# GSM.net
KiCad netlist of a schematic drawn in Altium Designer
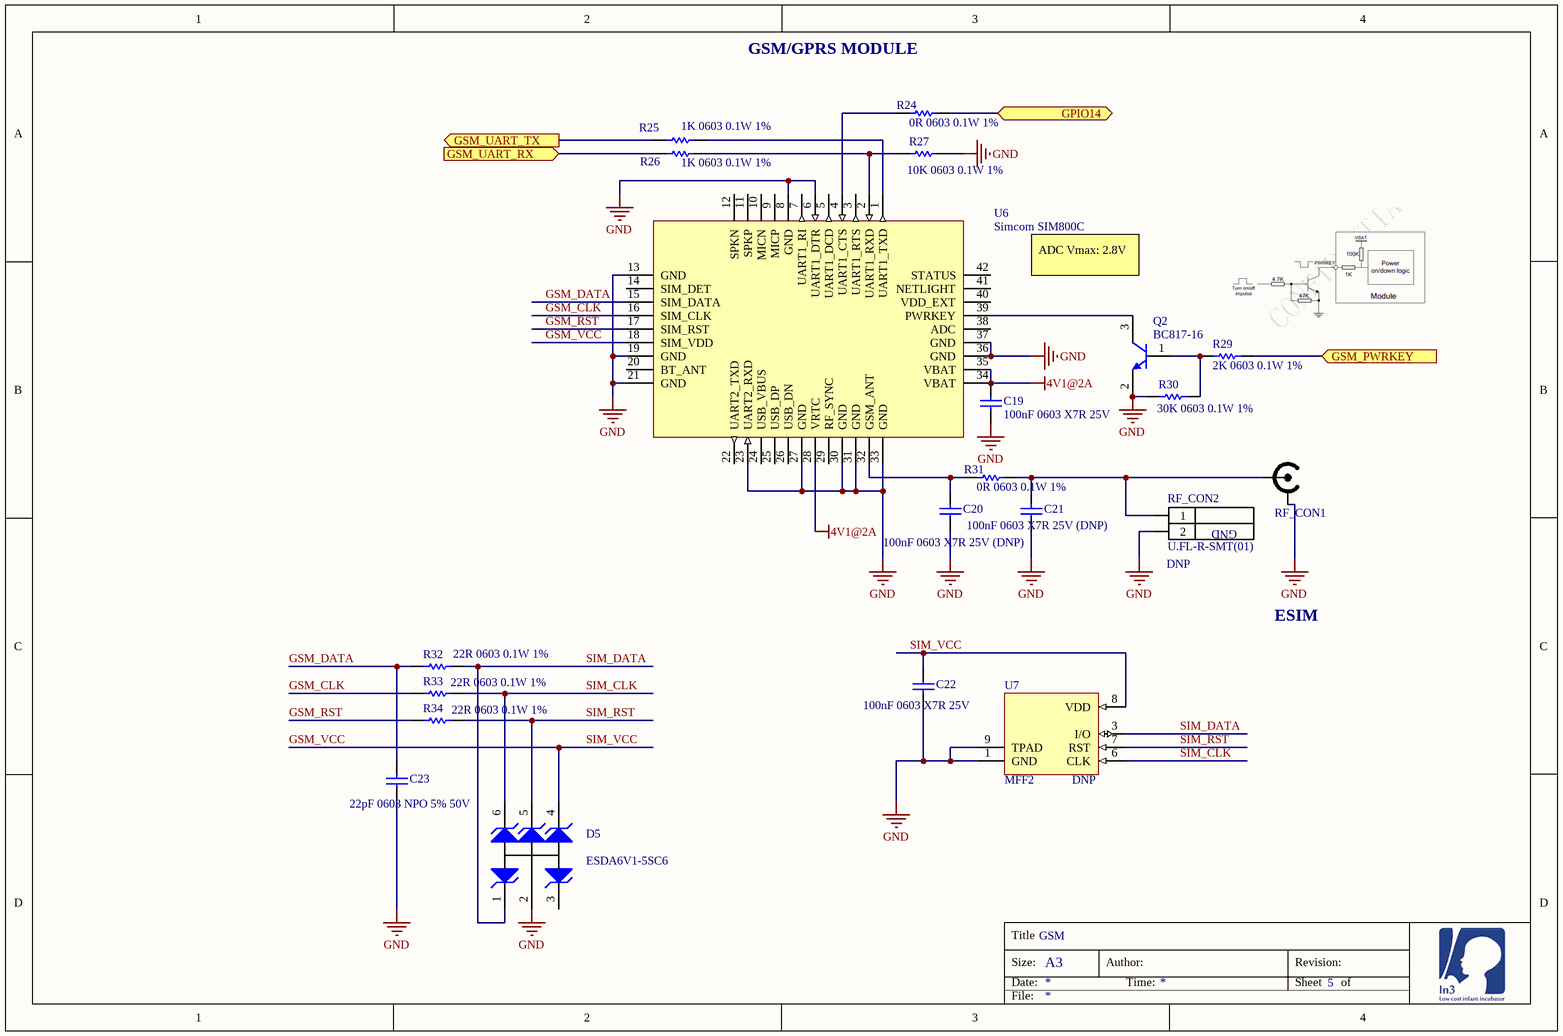
[diagram p0: GSM.SchDoc]

(export (version "E")
  (design (tool "Eeschema 10.0.6"))
  (components
    (comp (ref "C19")
      (value "100nF 0603 X7R 25V")
      (footprint "CAPC1608X60X35NL10T15")
      (libsource (lib "CommunityVault") (part "CMP-c41a0d2b65641bdd-3"))
    )
    (comp (ref "C20")
      (value "100nF 0603 X7R 25V (DNP)")
      (footprint "CAPC1608X60X35NL10T15")
      (libsource (lib "CommunityVault") (part "CMP-c41a0d2b65641bdd-3"))
    )
    (comp (ref "C21")
      (value "100nF 0603 X7R 25V (DNP)")
      (footprint "CAPC1608X60X35NL10T15")
      (libsource (lib "CommunityVault") (part "CMP-c41a0d2b65641bdd-3"))
    )
    (comp (ref "C22")
      (value "100nF 0603 X7R 25V")
      (footprint "CAPC1608X60X35NL10T15")
      (libsource (lib "CommunityVault") (part "CMP-c41a0d2b65641bdd-3"))
    )
    (comp (ref "C23")
      (value "22pF 0603 NPO 5% 50V")
      (footprint "CAPC1608X60X35NL10T15")
      (fields (field (name "MANUFACTURER PART NUMBER") "06035C220JAT2A"))
      (libsource (lib "CommunityVault") (part "CMP-126186-3"))
    )
    (comp (ref "D5")
      (value "ESDA6V1-5SC6")
      (footprint "MF06A_N")
      (description "ESDA Series 5 Channel 6.1 V 50 pF SMT Uni Directional Transil Array - SOT-23-6L")
      (libsource (lib "CommunityVault") (part "CMP-924f5b40f9684d88-1"))
    )
    (comp (ref "Q2")
      (value "BC817-16")
      (footprint "PCB-856332-1")
      (description "TRANS NPN 45V 500mA SMD SOT23-3")
      (libsource (lib "CommunityVault") (part "CMP-856332-3"))
    )
    (comp (ref "R24")
      (value "0R 0603 0.1W 1%")
      (footprint "RESC1609X55X30ML10T20")
      (libsource (lib "CommunityVault") (part "CMP-536b9a7387ce8cac-10"))
    )
    (comp (ref "R25")
      (value "1K 0603 0.1W 1%")
      (footprint "RESC1609X55X30ML10T20")
      (fields (field (name "MANUFACTURER PART NUMBER") "CR0603-FX-1001ELF"))
      (libsource (lib "CommunityVault") (part "CMP-a61f6f36030f79d8-4"))
    )
    (comp (ref "R26")
      (value "1K 0603 0.1W 1%")
      (footprint "RESC1609X55X30ML10T20")
      (fields (field (name "MANUFACTURER PART NUMBER") "CR0603-FX-1001ELF"))
      (libsource (lib "CommunityVault") (part "CMP-a61f6f36030f79d8-4"))
    )
    (comp (ref "R27")
      (value "10K 0603 0.1W 1%")
      (footprint "RESC1609X55X30ML10T20")
      (fields (field (name "TOLERANCE") "1%"))
      (libsource (lib "CommunityVault") (part "CMP-4716590-9"))
    )
    (comp (ref "R29")
      (value "2K 0603 0.1W 1%")
      (footprint "RESC1609X55X30ML10T20")
      (fields (field (name "TOLERANCE") "1%"))
      (libsource (lib "CommunityVault") (part "CMP-3655986-6"))
    )
    (comp (ref "R30")
      (value "30K 0603 0.1W 1%")
      (footprint "RESC1609X55X30ML10T20")
      (fields (field (name "TOLERANCE") "1%"))
      (libsource (lib "CommunityVault") (part "CMP-3655986-6"))
    )
    (comp (ref "R31")
      (value "0R 0603 0.1W 1%")
      (footprint "RESC1609X55X30ML10T20")
      (libsource (lib "CommunityVault") (part "CMP-536b9a7387ce8cac-10"))
    )
    (comp (ref "R32")
      (value "22R 0603 0.1W 1%")
      (footprint "RESC1609X55X30ML10T20")
      (fields (field (name "TOLERANCE") "1%"))
      (libsource (lib "CommunityVault") (part "CMP-1846194-8"))
    )
    (comp (ref "R33")
      (value "22R 0603 0.1W 1%")
      (footprint "RESC1609X55X30ML10T20")
      (fields (field (name "TOLERANCE") "1%"))
      (libsource (lib "CommunityVault") (part "CMP-1846194-8"))
    )
    (comp (ref "R34")
      (value "22R 0603 0.1W 1%")
      (footprint "RESC1609X55X30ML10T20")
      (fields (field (name "TOLERANCE") "1%"))
      (libsource (lib "CommunityVault") (part "CMP-1846194-8"))
    )
    (comp (ref "RF_CON1")
      (value "TE Connectivity 5-1814832-1")
      (footprint "PCB-gwgb3m8xi8a49txfo9ja-1")
      (description "RF Connectors / Coaxial Connectors Str PCB Skt")
      (libsource (lib "CommunityVault") (part "CMP-578319-10"))
    )
    (comp (ref "RF_CON2")
      (value "U.FL-R-SMT(01)")
      (footprint "PCB-ci0d6ius1xp1vci7q9ug-1")
      (description "Connector RF Coaxial Data Midget Coaxial")
      (fields (field (name "DNP") "DNP"))
      (libsource (lib "CommunityVault") (part "CMP-b06f7b3edcee6fa8-4"))
    )
    (comp (ref "U6")
      (value "Simcom SIM800C")
      (footprint "SIM800C")
      (description "Module: GSM/Bluetooth; GPRS; 2G; 1800MHz, 900MHz; 85.6kbps; SMD")
      (fields (field (name "MANUFACTURER PART NUMBER") "SIM800C"))
      (libsource (lib "FavoritesLibrary") (part "SYM-72dbb8ea0133ad1c-1"))
    )
    (comp (ref "U7")
      (value "MFF2")
      (footprint "SON127P600X95_HS-9N")
      (description "Embedded SIM card in MFF2")
      (fields (field (name "DNP") "DNP"))
      (libsource (lib "CommunityVault") (part "CMP-ce8f06c57f401148-2"))
    )
  )
  (nets
    (net (code "1") (name "/GPIO14") (class "Default")
      (node (ref "R24") (pin "2") (pinfunction "2_2") (pintype "passive"))
    )
    (net (code "2") (name "/GSM_CLK") (class "Default")
      (node (ref "R33") (pin "1") (pinfunction "1_1") (pintype "passive"))
      (node (ref "U6") (pin "16") (pinfunction "SIM_CLK_16") (pintype "passive"))
    )
    (net (code "3") (name "/GSM_DATA") (class "Default")
      (node (ref "C23") (pin "2") (pinfunction "2_2") (pintype "passive"))
      (node (ref "R32") (pin "1") (pinfunction "1_1") (pintype "passive"))
      (node (ref "U6") (pin "15") (pinfunction "SIM_DATA_15") (pintype "passive"))
    )
    (net (code "4") (name "/GSM_PWRKEY") (class "Default")
      (node (ref "R29") (pin "1") (pinfunction "1_1") (pintype "passive"))
    )
    (net (code "5") (name "/GSM_RST") (class "Default")
      (node (ref "R34") (pin "1") (pinfunction "1_1") (pintype "passive"))
      (node (ref "U6") (pin "17") (pinfunction "SIM_RST_17") (pintype "passive"))
    )
    (net (code "6") (name "/GSM_UART_RX") (class "Default")
      (node (ref "R26") (pin "1") (pinfunction "1_1") (pintype "passive"))
    )
    (net (code "7") (name "/GSM_UART_TX") (class "Default")
      (node (ref "R25") (pin "1") (pinfunction "1_1") (pintype "passive"))
    )
    (net (code "8") (name "/GSM_VCC") (class "Default")
      (node (ref "C22") (pin "2") (pinfunction "2_2") (pintype "passive"))
      (node (ref "D5") (pin "4") (pinfunction "A_4") (pintype "passive"))
      (node (ref "U6") (pin "18") (pinfunction "SIM_VDD_18") (pintype "passive"))
      (node (ref "U7") (pin "8") (pinfunction "VDD_8") (pintype "input"))
    )
    (net (code "9") (name "/SIM_CLK") (class "Default")
      (node (ref "D5") (pin "6") (pinfunction "A_6") (pintype "passive"))
      (node (ref "R33") (pin "2") (pinfunction "2_2") (pintype "passive"))
      (node (ref "U7") (pin "6") (pinfunction "CLK_6") (pintype "input"))
    )
    (net (code "10") (name "/SIM_DATA") (class "Default")
      (node (ref "D5") (pin "1") (pinfunction "K_1") (pintype "passive"))
      (node (ref "R32") (pin "2") (pinfunction "2_2") (pintype "passive"))
      (node (ref "U7") (pin "3") (pinfunction "I/O_3") (pintype "bidirectional"))
    )
    (net (code "11") (name "/SIM_RST") (class "Default")
      (node (ref "D5") (pin "5") (pinfunction "A_5") (pintype "passive"))
      (node (ref "R34") (pin "2") (pinfunction "2_2") (pintype "passive"))
      (node (ref "U7") (pin "7") (pinfunction "RST_7") (pintype "input"))
    )
    (net (code "12") (name "4V1@2A") (class "Default")
      (node (ref "C19") (pin "2") (pinfunction "2_2") (pintype "passive"))
      (node (ref "U6") (pin "28") (pinfunction "VRTC_28") (pintype "passive"))
      (node (ref "U6") (pin "34") (pinfunction "VBAT_34") (pintype "passive"))
      (node (ref "U6") (pin "35") (pinfunction "VBAT_35") (pintype "passive"))
    )
    (net (code "13") (name "GND") (class "Default")
      (node (ref "C19") (pin "1") (pinfunction "1_1") (pintype "passive"))
      (node (ref "C20") (pin "1") (pinfunction "1_1") (pintype "passive"))
      (node (ref "C21") (pin "1") (pinfunction "1_1") (pintype "passive"))
      (node (ref "C22") (pin "1") (pinfunction "1_1") (pintype "passive"))
      (node (ref "C23") (pin "1") (pinfunction "1_1") (pintype "passive"))
      (node (ref "D5") (pin "2") (pinfunction "K_2") (pintype "passive"))
      (node (ref "Q2") (pin "2") (pinfunction "E_2") (pintype "passive"))
      (node (ref "R27") (pin "2") (pinfunction "2_2") (pintype "passive"))
      (node (ref "R30") (pin "2") (pinfunction "2_2") (pintype "passive"))
      (node (ref "RF_CON1") (pin "2") (pinfunction "2_2") (pintype "passive"))
      (node (ref "RF_CON2") (pin "2") (pinfunction "2_2") (pintype "passive"))
      (node (ref "U6") (pin "13") (pinfunction "GND_13") (pintype "passive"))
      (node (ref "U6") (pin "19") (pinfunction "GND_19") (pintype "passive"))
      (node (ref "U6") (pin "21") (pinfunction "GND_21") (pintype "passive"))
      (node (ref "U6") (pin "23") (pinfunction "UART2_RXD_23") (pintype "input"))
      (node (ref "U6") (pin "27") (pinfunction "GND_27") (pintype "power_in"))
      (node (ref "U6") (pin "30") (pinfunction "GND_30") (pintype "power_in"))
      (node (ref "U6") (pin "31") (pinfunction "GND_31") (pintype "power_in"))
      (node (ref "U6") (pin "33") (pinfunction "GND_33") (pintype "power_in"))
      (node (ref "U6") (pin "36") (pinfunction "GND_36") (pintype "power_in"))
      (node (ref "U6") (pin "37") (pinfunction "GND_37") (pintype "power_in"))
      (node (ref "U6") (pin "6") (pinfunction "UART1_DTR_6") (pintype "input"))
      (node (ref "U6") (pin "8") (pinfunction "GND_8") (pintype "power_in"))
      (node (ref "U7") (pin "1") (pinfunction "GND_1") (pintype "power_in"))
      (node (ref "U7") (pin "9") (pinfunction "TPAD_9") (pintype "power_in"))
    )
    (net (code "14") (name "Net-(C21-Pad2)") (class "Default")
      (node (ref "C21") (pin "2") (pinfunction "2_2") (pintype "passive"))
      (node (ref "R31") (pin "2") (pinfunction "2_2") (pintype "passive"))
      (node (ref "RF_CON1") (pin "1") (pinfunction "1_1") (pintype "passive"))
      (node (ref "RF_CON2") (pin "1") (pinfunction "1_1") (pintype "passive"))
    )
    (net (code "15") (name "Net-(Q2-B)") (class "Default")
      (node (ref "Q2") (pin "1") (pinfunction "B_1") (pintype "passive"))
      (node (ref "R29") (pin "2") (pinfunction "2_2") (pintype "passive"))
      (node (ref "R30") (pin "1") (pinfunction "1_1") (pintype "passive"))
    )
    (net (code "16") (name "Net-(Q2-C)") (class "Default")
      (node (ref "Q2") (pin "3") (pinfunction "C_3") (pintype "passive"))
      (node (ref "U6") (pin "39") (pinfunction "PWRKEY_39") (pintype "passive"))
    )
    (net (code "17") (name "Net-(U6-GSM_ANT)") (class "Default")
      (node (ref "C20") (pin "2") (pinfunction "2_2") (pintype "passive"))
      (node (ref "R31") (pin "1") (pinfunction "1_1") (pintype "passive"))
      (node (ref "U6") (pin "32") (pinfunction "GSM_ANT_32") (pintype "passive"))
    )
    (net (code "18") (name "Net-(U6-UART1_CTS)") (class "Default")
      (node (ref "R24") (pin "1") (pinfunction "1_1") (pintype "passive"))
      (node (ref "U6") (pin "4") (pinfunction "UART1_CTS_4") (pintype "input"))
    )
    (net (code "19") (name "Net-(U6-UART1_RXD)") (class "Default")
      (node (ref "R26") (pin "2") (pinfunction "2_2") (pintype "passive"))
      (node (ref "R27") (pin "1") (pinfunction "1_1") (pintype "passive"))
      (node (ref "U6") (pin "2") (pinfunction "UART1_RXD_2") (pintype "input"))
    )
    (net (code "20") (name "Net-(U6-UART1_TXD)") (class "Default")
      (node (ref "R25") (pin "2") (pinfunction "2_2") (pintype "passive"))
      (node (ref "U6") (pin "1") (pinfunction "UART1_TXD_1") (pintype "output"))
    )
    (net (code "21") (name "unconnected-(D5-K-Pad3)") (class "Default")
      (node (ref "D5") (pin "3") (pinfunction "K_3") (pintype "passive"))
    )
    (net (code "22") (name "unconnected-(U6-ADC-Pad38)") (class "Default")
      (node (ref "U6") (pin "38") (pinfunction "ADC_38") (pintype "passive"))
    )
    (net (code "23") (name "unconnected-(U6-BT_ANT-Pad20)") (class "Default")
      (node (ref "U6") (pin "20") (pinfunction "BT_ANT_20") (pintype "passive"))
    )
    (net (code "24") (name "unconnected-(U6-MICN-Pad10)") (class "Default")
      (node (ref "U6") (pin "10") (pinfunction "MICN_10") (pintype "passive"))
    )
    (net (code "25") (name "unconnected-(U6-MICP-Pad9)") (class "Default")
      (node (ref "U6") (pin "9") (pinfunction "MICP_9") (pintype "passive"))
    )
    (net (code "26") (name "unconnected-(U6-NETLIGHT-Pad41)") (class "Default")
      (node (ref "U6") (pin "41") (pinfunction "NETLIGHT_41") (pintype "passive"))
    )
    (net (code "27") (name "unconnected-(U6-RF_SYNC-Pad29)") (class "Default")
      (node (ref "U6") (pin "29") (pinfunction "RF_SYNC_29") (pintype "passive"))
    )
    (net (code "28") (name "unconnected-(U6-SIM_DET-Pad14)") (class "Default")
      (node (ref "U6") (pin "14") (pinfunction "SIM_DET_14") (pintype "passive"))
    )
    (net (code "29") (name "unconnected-(U6-SPKN-Pad12)") (class "Default")
      (node (ref "U6") (pin "12") (pinfunction "SPKN_12") (pintype "passive"))
    )
    (net (code "30") (name "unconnected-(U6-SPKP-Pad11)") (class "Default")
      (node (ref "U6") (pin "11") (pinfunction "SPKP_11") (pintype "passive"))
    )
    (net (code "31") (name "unconnected-(U6-STATUS-Pad42)") (class "Default")
      (node (ref "U6") (pin "42") (pinfunction "STATUS_42") (pintype "passive"))
    )
    (net (code "32") (name "unconnected-(U6-UART1_DCD-Pad5)") (class "Default")
      (node (ref "U6") (pin "5") (pinfunction "UART1_DCD_5") (pintype "output"))
    )
    (net (code "33") (name "unconnected-(U6-UART1_RI-Pad7)") (class "Default")
      (node (ref "U6") (pin "7") (pinfunction "UART1_RI_7") (pintype "output"))
    )
    (net (code "34") (name "unconnected-(U6-UART1_RTS-Pad3)") (class "Default")
      (node (ref "U6") (pin "3") (pinfunction "UART1_RTS_3") (pintype "output"))
    )
    (net (code "35") (name "unconnected-(U6-UART2_TXD-Pad22)") (class "Default")
      (node (ref "U6") (pin "22") (pinfunction "UART2_TXD_22") (pintype "output"))
    )
    (net (code "36") (name "unconnected-(U6-USB_DN-Pad26)") (class "Default")
      (node (ref "U6") (pin "26") (pinfunction "USB_DN_26") (pintype "passive"))
    )
    (net (code "37") (name "unconnected-(U6-USB_DP-Pad25)") (class "Default")
      (node (ref "U6") (pin "25") (pinfunction "USB_DP_25") (pintype "passive"))
    )
    (net (code "38") (name "unconnected-(U6-USB_VBUS-Pad24)") (class "Default")
      (node (ref "U6") (pin "24") (pinfunction "USB_VBUS_24") (pintype "passive"))
    )
    (net (code "39") (name "unconnected-(U6-VDD_EXT-Pad40)") (class "Default")
      (node (ref "U6") (pin "40") (pinfunction "VDD_EXT_40") (pintype "passive"))
    )
  )
)
